# SCH_Aquaguard-system_2026-05-28.net
KiCad netlist of a schematic drawn in EasyEDA
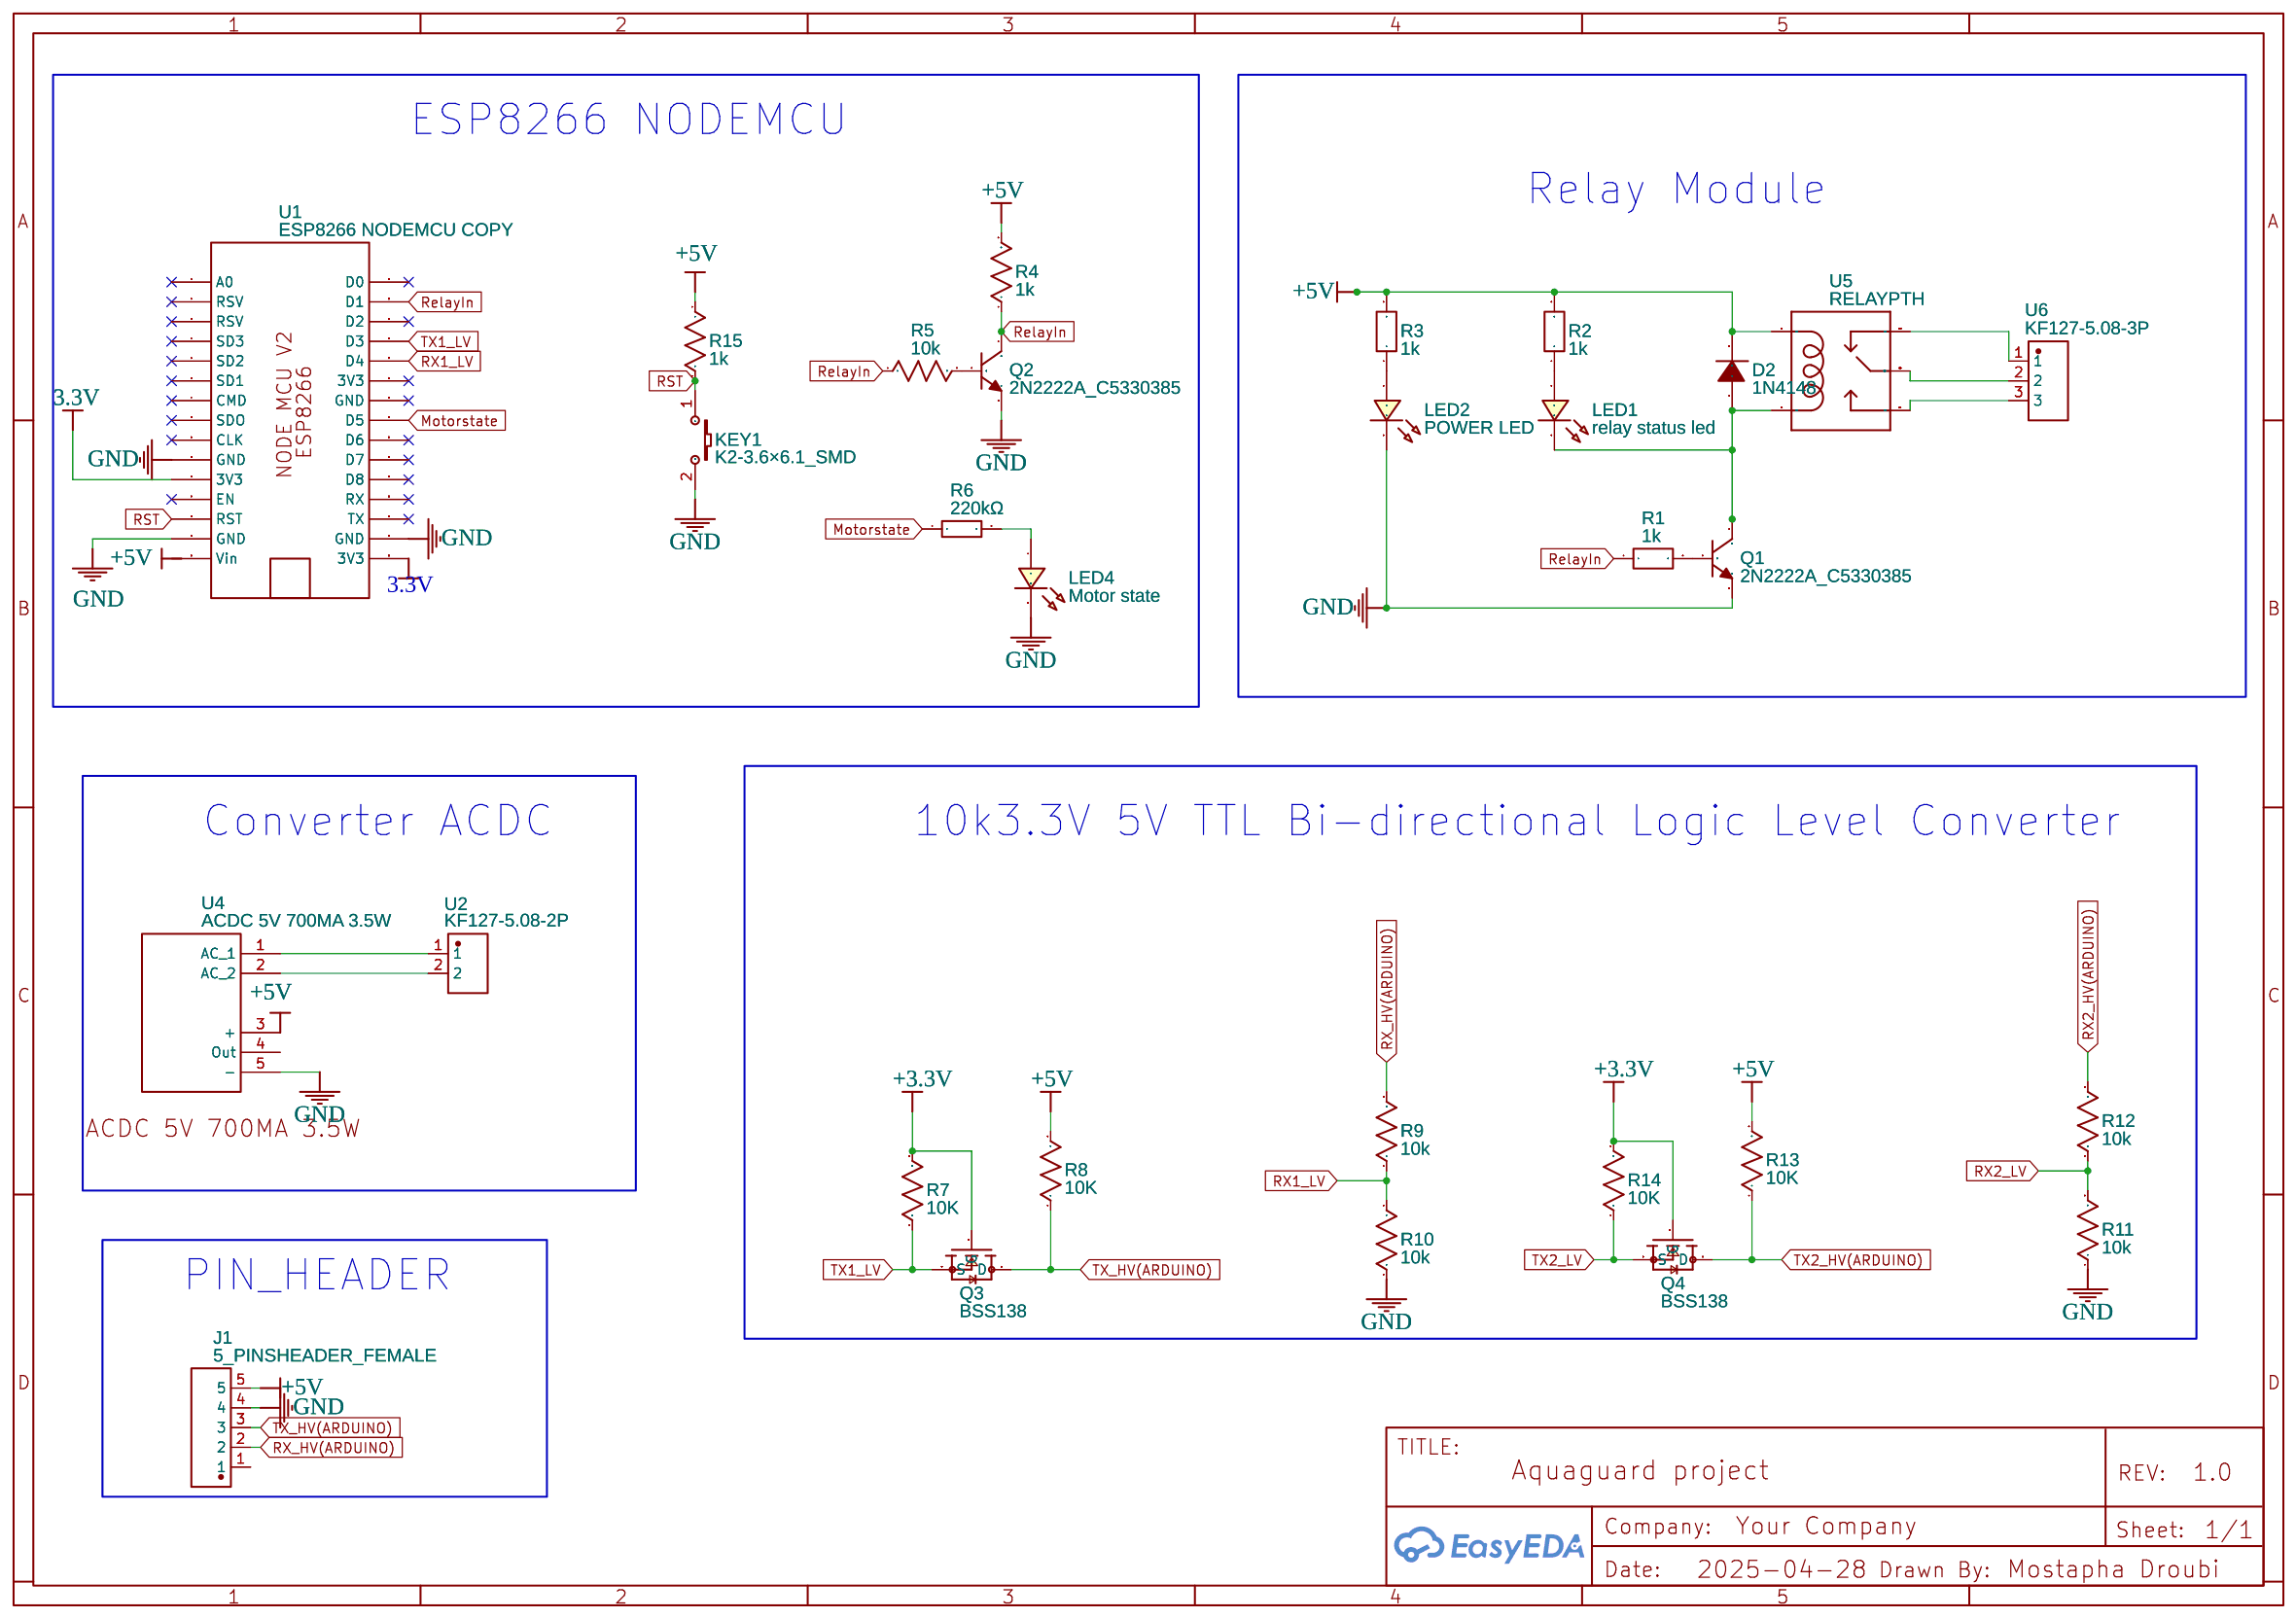
[diagram p0: schematic sheet]

(export (version "E")
  (design (tool "Eeschema 10.0.6"))
  (components
    (comp (ref "D2")
      (value "1N4148")
      (fields (field (name "Manufacturer") "ST(先科)"))
      (libsource (lib "") (part "1N4148"))
    )
    (comp (ref "J1") (value "5_PINSHEADER_FEMALE") (libsource (lib "") (part "5_PINSHEADER_FEMALE")))
    (comp (ref "KEY1")
      (value "K2-3.6×6.1_SMD")
      (fields (field (name "Manufacturer Part") "K2-1107ST-A4SW-06"))
      (libsource (lib "") (part "K2-3.6×6.1_SMD"))
    )
    (comp (ref "LED1")
      (value "relay status led")
      (fields
        (field (name "Manufacturer Part") "204-10SYGD/S530-E3")
        (field (name "Manufacturer") "EVERLIGHT(台湾亿光)")
      )
      (libsource (lib "") (part "LED-TH-3mm_G"))
    )
    (comp (ref "LED2")
      (value "POWER LED")
      (fields
        (field (name "Manufacturer Part") "19-217/R6C-AL1M2VY/3T")
        (field (name "Manufacturer") "EVERLIGHT(台湾亿光)")
      )
      (libsource (lib "") (part "LED-0603_R"))
    )
    (comp (ref "LED4")
      (value "Motor state")
      (fields (field (name "Manufacturer Part") "D-B080508B1-KS2") (field (name "Manufacturer") "方舟 ARKLED"))
      (libsource (lib "") (part "LED-0805_B"))
    )
    (comp (ref "Q1")
      (value "2N2222A_C5330385")
      (fields (field (name "Manufacturer Part") "2N2222A") (field (name "Manufacturer") "Slkor(萨科微)"))
      (libsource (lib "") (part "2N2222A_C5330385"))
    )
    (comp (ref "Q2")
      (value "2N2222A_C5330385")
      (fields (field (name "Manufacturer Part") "2N2222A") (field (name "Manufacturer") "Slkor(萨科微)"))
      (libsource (lib "") (part "2N2222A_C5330385"))
    )
    (comp (ref "Q3")
      (value "BSS138")
      (fields (field (name "Manufacturer") "ON Semiconductor"))
      (libsource (lib "") (part "BSS138"))
    )
    (comp (ref "Q4")
      (value "BSS138")
      (fields (field (name "Manufacturer") "ON Semiconductor"))
      (libsource (lib "") (part "BSS138"))
    )
    (comp (ref "R1") (value "1k") (libsource (lib "") (part "R_0201_EU_1")))
    (comp (ref "R2") (value "1k") (libsource (lib "") (part "R_0201_EU")))
    (comp (ref "R3") (value "1k") (libsource (lib "") (part "R_0201_EU")))
    (comp (ref "R4") (value "1k") (libsource (lib "") (part "R_0603_US_1")))
    (comp (ref "R5") (value "10k") (libsource (lib "") (part "R_0603_US")))
    (comp (ref "R6")
      (value "220kΩ")
      (fields (field (name "Manufacturer Part") "RC0805JR-07220KL") (field (name "Manufacturer") "YAGEO(国巨)"))
      (libsource (lib "") (part "RC0805JR-07220KL"))
    )
    (comp (ref "R7") (value "10K") (libsource (lib "") (part "R_0603_US_1")))
    (comp (ref "R8") (value "10K") (libsource (lib "") (part "R_0603_US_1")))
    (comp (ref "R9") (value "10k") (libsource (lib "") (part "R_0603_US_1")))
    (comp (ref "R10") (value "10k") (libsource (lib "") (part "R_0603_US_1")))
    (comp (ref "R11") (value "10k") (libsource (lib "") (part "R_0603_US_1")))
    (comp (ref "R12") (value "10k") (libsource (lib "") (part "R_0603_US_1")))
    (comp (ref "R13") (value "10K") (libsource (lib "") (part "R_0603_US_1")))
    (comp (ref "R14") (value "10K") (libsource (lib "") (part "R_0603_US_1")))
    (comp (ref "R15") (value "1k") (libsource (lib "") (part "R_0603_US_2")))
    (comp (ref "U1") (value "ESP8266 NODEMCU COPY") (libsource (lib "") (part "ESP8266 NODEMCU COPY")))
    (comp (ref "U2")
      (value "KF127-5.08-2P")
      (fields (field (name "Manufacturer") "KEFA(科发)"))
      (libsource (lib "") (part "KF127-5.08-2P"))
    )
    (comp (ref "U4") (value "ACDC 5V 700MA 3.5W") (libsource (lib "") (part "ACDC 5V 700MA 3.5W")))
    (comp (ref "U5") (value "RELAYPTH") (libsource (lib "") (part "RELAYPTH")))
    (comp (ref "U6")
      (value "KF127-5.08-3P")
      (fields (field (name "Manufacturer") "KEFA(科发)"))
      (libsource (lib "") (part "KF127-5.08-3P"))
    )
  )
  (nets
    (net (code "1") (name "+3.3V") (class "Default")
      (node (ref "Q3") (pin "G") (pinfunction "G_G") (pintype "bidirectional"))
      (node (ref "Q4") (pin "G") (pinfunction "G_G") (pintype "bidirectional"))
      (node (ref "R14") (pin "2") (pinfunction "2_2") (pintype "unspecified"))
      (node (ref "R7") (pin "2") (pinfunction "2_2") (pintype "unspecified"))
    )
    (net (code "2") (name "+5V") (class "Default")
      (node (ref "D2") (pin "2") (pinfunction "C_2") (pintype "unspecified"))
      (node (ref "J1") (pin "5") (pinfunction "5_5") (pintype "unspecified"))
      (node (ref "R13") (pin "2") (pinfunction "2_2") (pintype "unspecified"))
      (node (ref "R15") (pin "1") (pinfunction "1_1") (pintype "unspecified"))
      (node (ref "R2") (pin "2") (pinfunction "2_2") (pintype "unspecified"))
      (node (ref "R3") (pin "2") (pinfunction "2_2") (pintype "unspecified"))
      (node (ref "R4") (pin "2") (pinfunction "2_2") (pintype "unspecified"))
      (node (ref "R8") (pin "2") (pinfunction "2_2") (pintype "unspecified"))
      (node (ref "U1") (pin "15") (pinfunction "Vin_15") (pintype "unspecified"))
      (node (ref "U4") (pin "3") (pinfunction "+_3") (pintype "unspecified"))
      (node (ref "U5") (pin "COIL1") (pinfunction "COIL1_COIL1") (pintype "unspecified"))
    )
    (net (code "3") (name "3.3V") (class "Default")
      (node (ref "U1") (pin "11") (pinfunction "3V3_11") (pintype "unspecified"))
      (node (ref "U1") (pin "16") (pinfunction "3V3_16") (pintype "unspecified"))
    )
    (net (code "4") (name "GND") (class "Default")
      (node (ref "J1") (pin "4") (pinfunction "4_4") (pintype "unspecified"))
      (node (ref "KEY1") (pin "2") (pinfunction "2_2") (pintype "unspecified"))
      (node (ref "LED2") (pin "2") (pinfunction "2_2") (pintype "unspecified"))
      (node (ref "LED4") (pin "2") (pinfunction "2_2") (pintype "unspecified"))
      (node (ref "Q1") (pin "3") (pinfunction "E_3") (pintype "unspecified"))
      (node (ref "Q2") (pin "3") (pinfunction "E_3") (pintype "unspecified"))
      (node (ref "R10") (pin "1") (pinfunction "1_1") (pintype "unspecified"))
      (node (ref "R11") (pin "1") (pinfunction "1_1") (pintype "unspecified"))
      (node (ref "U1") (pin "10") (pinfunction "GND_10") (pintype "unspecified"))
      (node (ref "U1") (pin "14") (pinfunction "GND_14") (pintype "unspecified"))
      (node (ref "U1") (pin "17") (pinfunction "GND_17") (pintype "unspecified"))
      (node (ref "U4") (pin "5") (pinfunction "-_5") (pintype "unspecified"))
    )
    (net (code "5") (name "Motorstate") (class "Default")
      (node (ref "R6") (pin "1") (pinfunction "1_1") (pintype "input"))
      (node (ref "U1") (pin "23") (pinfunction "D5_23") (pintype "unspecified"))
    )
    (net (code "6") (name "Net-(D2-A)") (class "Default")
      (node (ref "D2") (pin "1") (pinfunction "A_1") (pintype "unspecified"))
      (node (ref "LED1") (pin "2") (pinfunction "2_2") (pintype "unspecified"))
      (node (ref "Q1") (pin "1") (pinfunction "C_1") (pintype "unspecified"))
      (node (ref "U5") (pin "COIL0") (pinfunction "COIL0_COIL0") (pintype "unspecified"))
    )
    (net (code "7") (name "Net-(LED1-Pad1)") (class "Default")
      (node (ref "LED1") (pin "1") (pinfunction "1_1") (pintype "unspecified"))
      (node (ref "R2") (pin "1") (pinfunction "1_1") (pintype "unspecified"))
    )
    (net (code "8") (name "Net-(LED2-Pad1)") (class "Default")
      (node (ref "LED2") (pin "1") (pinfunction "1_1") (pintype "unspecified"))
      (node (ref "R3") (pin "1") (pinfunction "1_1") (pintype "unspecified"))
    )
    (net (code "9") (name "Net-(LED4-Pad1)") (class "Default")
      (node (ref "LED4") (pin "1") (pinfunction "1_1") (pintype "unspecified"))
      (node (ref "R6") (pin "2") (pinfunction "2_2") (pintype "input"))
    )
    (net (code "10") (name "Net-(Q1-B)") (class "Default")
      (node (ref "Q1") (pin "2") (pinfunction "B_2") (pintype "unspecified"))
      (node (ref "R1") (pin "2") (pinfunction "2_2") (pintype "unspecified"))
    )
    (net (code "11") (name "Net-(Q2-B)") (class "Default")
      (node (ref "Q2") (pin "2") (pinfunction "B_2") (pintype "unspecified"))
      (node (ref "R5") (pin "2") (pinfunction "2_2") (pintype "unspecified"))
    )
    (net (code "12") (name "Net-(U4-AC_1)") (class "Default")
      (node (ref "U2") (pin "1") (pinfunction "1_1") (pintype "unspecified"))
      (node (ref "U4") (pin "1") (pinfunction "AC_1_1") (pintype "unspecified"))
    )
    (net (code "13") (name "Net-(U4-AC_2)") (class "Default")
      (node (ref "U2") (pin "2") (pinfunction "2_2") (pintype "unspecified"))
      (node (ref "U4") (pin "2") (pinfunction "AC_2_2") (pintype "unspecified"))
    )
    (net (code "14") (name "Net-(U5-PadSWCOMMON)") (class "Default")
      (node (ref "U5") (pin "SWCOMMON") (pinfunction "SWCOMMON_SWCOMMON") (pintype "unspecified"))
      (node (ref "U6") (pin "2") (pinfunction "2_2") (pintype "unspecified"))
    )
    (net (code "15") (name "Net-(U5-PadSWOPEN)") (class "Default")
      (node (ref "U5") (pin "SWOPEN") (pinfunction "SWOPEN_SWOPEN") (pintype "unspecified"))
      (node (ref "U6") (pin "3") (pinfunction "3_3") (pintype "unspecified"))
    )
    (net (code "16") (name "Net-(U5-SWCLOSE)") (class "Default")
      (node (ref "U5") (pin "SWCLOSED") (pinfunction "SWCLOSE_SWCLOSED") (pintype "unspecified"))
      (node (ref "U6") (pin "1") (pinfunction "1_1") (pintype "unspecified"))
    )
    (net (code "17") (name "RST") (class "Default")
      (node (ref "KEY1") (pin "1") (pinfunction "1_1") (pintype "unspecified"))
      (node (ref "R15") (pin "2") (pinfunction "2_2") (pintype "unspecified"))
      (node (ref "U1") (pin "13") (pinfunction "RST_13") (pintype "unspecified"))
    )
    (net (code "18") (name "RX1_LV") (class "Default")
      (node (ref "R10") (pin "2") (pinfunction "2_2") (pintype "unspecified"))
      (node (ref "R9") (pin "1") (pinfunction "1_1") (pintype "unspecified"))
      (node (ref "U1") (pin "26") (pinfunction "D4_26") (pintype "unspecified"))
    )
    (net (code "19") (name "RX2_HV(ARDUINO)") (class "Default")
      (node (ref "R12") (pin "2") (pinfunction "2_2") (pintype "unspecified"))
    )
    (net (code "20") (name "RX2_LV") (class "Default")
      (node (ref "R11") (pin "2") (pinfunction "2_2") (pintype "unspecified"))
      (node (ref "R12") (pin "1") (pinfunction "1_1") (pintype "unspecified"))
    )
    (net (code "21") (name "RX_HV(ARDUINO)") (class "Default")
      (node (ref "J1") (pin "2") (pinfunction "2_2") (pintype "unspecified"))
      (node (ref "R9") (pin "2") (pinfunction "2_2") (pintype "unspecified"))
    )
    (net (code "22") (name "RelayIn") (class "Default")
      (node (ref "Q2") (pin "1") (pinfunction "C_1") (pintype "unspecified"))
      (node (ref "R1") (pin "1") (pinfunction "1_1") (pintype "unspecified"))
      (node (ref "R4") (pin "1") (pinfunction "1_1") (pintype "unspecified"))
      (node (ref "R5") (pin "1") (pinfunction "1_1") (pintype "unspecified"))
      (node (ref "U1") (pin "29") (pinfunction "D1_29") (pintype "unspecified"))
    )
    (net (code "23") (name "TX1_LV") (class "Default")
      (node (ref "Q3") (pin "S") (pinfunction "S_S") (pintype "bidirectional"))
      (node (ref "R7") (pin "1") (pinfunction "1_1") (pintype "unspecified"))
      (node (ref "U1") (pin "27") (pinfunction "D3_27") (pintype "unspecified"))
    )
    (net (code "24") (name "TX2_HV(ARDUINO)") (class "Default")
      (node (ref "Q4") (pin "D") (pinfunction "D_D") (pintype "bidirectional"))
      (node (ref "R13") (pin "1") (pinfunction "1_1") (pintype "unspecified"))
    )
    (net (code "25") (name "TX2_LV") (class "Default")
      (node (ref "Q4") (pin "S") (pinfunction "S_S") (pintype "bidirectional"))
      (node (ref "R14") (pin "1") (pinfunction "1_1") (pintype "unspecified"))
    )
    (net (code "26") (name "TX_HV(ARDUINO)") (class "Default")
      (node (ref "J1") (pin "3") (pinfunction "3_3") (pintype "unspecified"))
      (node (ref "Q3") (pin "D") (pinfunction "D_D") (pintype "bidirectional"))
      (node (ref "R8") (pin "1") (pinfunction "1_1") (pintype "unspecified"))
    )
    (net (code "27") (name "unconnected-(J1-Pad1)") (class "Default")
      (node (ref "J1") (pin "1") (pinfunction "1_1") (pintype "unspecified"))
    )
    (net (code "28") (name "unconnected-(U1-3V3-Pad25)") (class "Default")
      (node (ref "U1") (pin "25") (pinfunction "3V3_25") (pintype "unspecified+no_connect"))
    )
    (net (code "29") (name "unconnected-(U1-A0-Pad1)") (class "Default")
      (node (ref "U1") (pin "1") (pinfunction "A0_1") (pintype "unspecified+no_connect"))
    )
    (net (code "30") (name "unconnected-(U1-CLK-Pad9)") (class "Default")
      (node (ref "U1") (pin "9") (pinfunction "CLK_9") (pintype "unspecified+no_connect"))
    )
    (net (code "31") (name "unconnected-(U1-CMD-Pad7)") (class "Default")
      (node (ref "U1") (pin "7") (pinfunction "CMD_7") (pintype "unspecified+no_connect"))
    )
    (net (code "32") (name "unconnected-(U1-D0-Pad30)") (class "Default")
      (node (ref "U1") (pin "30") (pinfunction "D0_30") (pintype "unspecified+no_connect"))
    )
    (net (code "33") (name "unconnected-(U1-D2-Pad28)") (class "Default")
      (node (ref "U1") (pin "28") (pinfunction "D2_28") (pintype "unspecified+no_connect"))
    )
    (net (code "34") (name "unconnected-(U1-D6-Pad22)") (class "Default")
      (node (ref "U1") (pin "22") (pinfunction "D6_22") (pintype "unspecified+no_connect"))
    )
    (net (code "35") (name "unconnected-(U1-D7-Pad21)") (class "Default")
      (node (ref "U1") (pin "21") (pinfunction "D7_21") (pintype "unspecified+no_connect"))
    )
    (net (code "36") (name "unconnected-(U1-D8-Pad20)") (class "Default")
      (node (ref "U1") (pin "20") (pinfunction "D8_20") (pintype "unspecified+no_connect"))
    )
    (net (code "37") (name "unconnected-(U1-EN-Pad12)") (class "Default")
      (node (ref "U1") (pin "12") (pinfunction "EN_12") (pintype "unspecified+no_connect"))
    )
    (net (code "38") (name "unconnected-(U1-GND-Pad24)") (class "Default")
      (node (ref "U1") (pin "24") (pinfunction "GND_24") (pintype "unspecified+no_connect"))
    )
    (net (code "39") (name "unconnected-(U1-RSV-Pad2)") (class "Default")
      (node (ref "U1") (pin "2") (pinfunction "RSV_2") (pintype "unspecified+no_connect"))
    )
    (net (code "40") (name "unconnected-(U1-RSV-Pad3)") (class "Default")
      (node (ref "U1") (pin "3") (pinfunction "RSV_3") (pintype "unspecified+no_connect"))
    )
    (net (code "41") (name "unconnected-(U1-RX-Pad19)") (class "Default")
      (node (ref "U1") (pin "19") (pinfunction "RX_19") (pintype "unspecified+no_connect"))
    )
    (net (code "42") (name "unconnected-(U1-SD1-Pad6)") (class "Default")
      (node (ref "U1") (pin "6") (pinfunction "SD1_6") (pintype "unspecified+no_connect"))
    )
    (net (code "43") (name "unconnected-(U1-SD2-Pad5)") (class "Default")
      (node (ref "U1") (pin "5") (pinfunction "SD2_5") (pintype "unspecified+no_connect"))
    )
    (net (code "44") (name "unconnected-(U1-SD3-Pad4)") (class "Default")
      (node (ref "U1") (pin "4") (pinfunction "SD3_4") (pintype "unspecified+no_connect"))
    )
    (net (code "45") (name "unconnected-(U1-SDO-Pad8)") (class "Default")
      (node (ref "U1") (pin "8") (pinfunction "SDO_8") (pintype "unspecified+no_connect"))
    )
    (net (code "46") (name "unconnected-(U1-TX-Pad18)") (class "Default")
      (node (ref "U1") (pin "18") (pinfunction "TX_18") (pintype "unspecified+no_connect"))
    )
    (net (code "47") (name "unconnected-(U4-Out-Pad4)") (class "Default")
      (node (ref "U4") (pin "4") (pinfunction "Out_4") (pintype "unspecified"))
    )
  )
)
